# power_supply-TPS54531.net
KiCad netlist of a schematic drawn in EAGLE
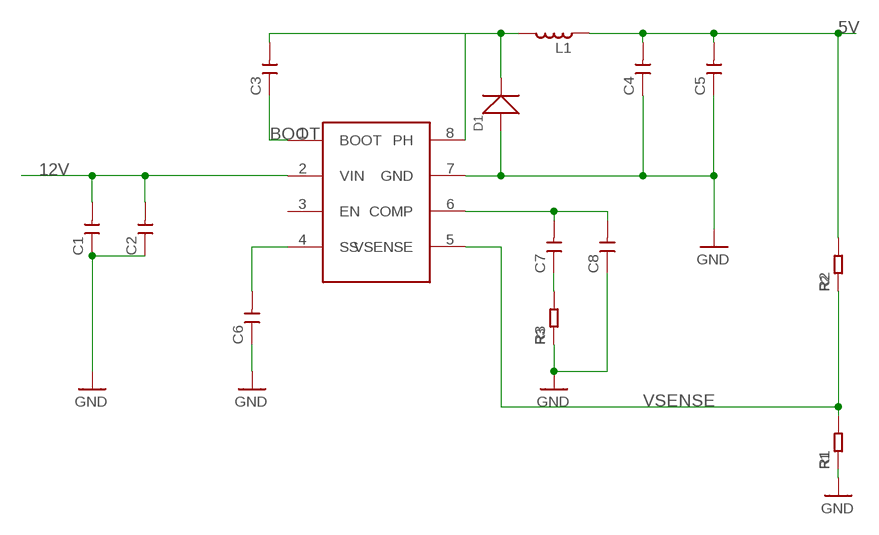
[diagram p0: schematic, sheet 1]

(export (version "E")
  (design (tool "Eeschema 10.0.6"))
  (components
    (comp (ref "C1")
      (value "CAP-CERAMIC-SMD0805")
      (footprint "eagle-import:0805")
      (libsource (lib "eagle-import") (part "CAP-CERAMIC-SMD0805"))
    )
    (comp (ref "C2")
      (value "CAP-CERAMIC-SMD0805")
      (footprint "eagle-import:0805")
      (libsource (lib "eagle-import") (part "CAP-CERAMIC-SMD0805"))
    )
    (comp (ref "C3")
      (value "CAP-CERAMIC-SMD0805")
      (footprint "eagle-import:0805")
      (libsource (lib "eagle-import") (part "CAP-CERAMIC-SMD0805"))
    )
    (comp (ref "C4")
      (value "CAP-CERAMIC-SMD0805")
      (footprint "eagle-import:0805")
      (libsource (lib "eagle-import") (part "CAP-CERAMIC-SMD0805"))
    )
    (comp (ref "C5")
      (value "CAP-CERAMIC-SMD0805")
      (footprint "eagle-import:0805")
      (libsource (lib "eagle-import") (part "CAP-CERAMIC-SMD0805"))
    )
    (comp (ref "C6")
      (value "CAP-CERAMIC-SMD0805")
      (footprint "eagle-import:0805")
      (libsource (lib "eagle-import") (part "CAP-CERAMIC-SMD0805"))
    )
    (comp (ref "C7")
      (value "CAP-CERAMIC-SMD0805")
      (footprint "eagle-import:0805")
      (libsource (lib "eagle-import") (part "CAP-CERAMIC-SMD0805"))
    )
    (comp (ref "C8")
      (value "CAP-CERAMIC-SMD0805")
      (footprint "eagle-import:0805")
      (libsource (lib "eagle-import") (part "CAP-CERAMIC-SMD0805"))
    )
    (comp (ref "D1")
      (value "SMD-DIODE-SCHOTTKY-28V-5A(DO-214AA)DO-214AC")
      (footprint "eagle-import:SMA-DO214AC")
      (fields (field (name "MANUFACTURER") "Comchip Technologies") (field (name "PARTNO") "CDBA540-HF"))
      (libsource (lib "eagle-import") (part "SMD-DIODE-SCHOTTKY-28V-5A(DO-214AA)DO-214AC"))
    )
    (comp (ref "L1")
      (value "IND-TDK-SPM6530T")
      (footprint "eagle-import:IND_TDK_7.1X6.5")
      (fields (field (name "MANUFACTURER") "TDK") (field (name "PARTNO") "SPM6530T-4R7M "))
      (libsource (lib "eagle-import") (part "IND-TDK-SPM6530T"))
    )
    (comp (ref "R1")
      (value "RES-SMD-0805")
      (footprint "eagle-import:0805")
      (libsource (lib "eagle-import") (part "RES-SMD-0805"))
    )
    (comp (ref "R2")
      (value "RES-SMD-0805")
      (footprint "eagle-import:0805")
      (libsource (lib "eagle-import") (part "RES-SMD-0805"))
    )
    (comp (ref "R3")
      (value "RES-SMD-0805")
      (footprint "eagle-import:0805")
      (libsource (lib "eagle-import") (part "RES-SMD-0805"))
    )
    (comp (ref "U$1")
      (value "TPS54531SOIC8")
      (footprint "eagle-import:SOIC8")
      (fields (field (name "MANUFACTURER") "TEXAS INSTRUMENTS") (field (name "PARTNO") "TPS54531DDAR"))
      (libsource (lib "eagle-import") (part "TPS54531SOIC8"))
    )
  )
  (nets
    (net (code "1") (name "/5V") (class "Default")
      (node (ref "C4") (pin "2") (pinfunction "2_2") (pintype "passive"))
      (node (ref "C5") (pin "2") (pinfunction "2_2") (pintype "passive"))
      (node (ref "L1") (pin "1") (pinfunction "1_1") (pintype "passive"))
      (node (ref "R2") (pin "2") (pinfunction "2_2") (pintype "passive"))
    )
    (net (code "2") (name "/12V") (class "Default")
      (node (ref "C1") (pin "2") (pinfunction "2_2") (pintype "passive"))
      (node (ref "C2") (pin "2") (pinfunction "2_2") (pintype "passive"))
      (node (ref "U$1") (pin "2") (pinfunction "VIN_2") (pintype "power_in"))
    )
    (net (code "3") (name "/BOOT") (class "Default")
      (node (ref "C3") (pin "1") (pinfunction "1_1") (pintype "passive"))
      (node (ref "U$1") (pin "1") (pinfunction "BOOT_1") (pintype "bidirectional"))
    )
    (net (code "4") (name "/VSENSE") (class "Default")
      (node (ref "R1") (pin "2") (pinfunction "2_2") (pintype "passive"))
      (node (ref "R2") (pin "1") (pinfunction "1_1") (pintype "passive"))
      (node (ref "U$1") (pin "5") (pinfunction "VSENSE_5") (pintype "bidirectional"))
    )
    (net (code "5") (name "GND") (class "Default")
      (node (ref "C1") (pin "1") (pinfunction "1_1") (pintype "passive"))
      (node (ref "C2") (pin "1") (pinfunction "1_1") (pintype "passive"))
      (node (ref "C4") (pin "1") (pinfunction "1_1") (pintype "passive"))
      (node (ref "C5") (pin "1") (pinfunction "1_1") (pintype "passive"))
      (node (ref "C6") (pin "1") (pinfunction "1_1") (pintype "passive"))
      (node (ref "C8") (pin "1") (pinfunction "1_1") (pintype "passive"))
      (node (ref "D1") (pin "A") (pinfunction "+_A") (pintype "passive"))
      (node (ref "R1") (pin "1") (pinfunction "1_1") (pintype "passive"))
      (node (ref "R3") (pin "1") (pinfunction "1_1") (pintype "passive"))
      (node (ref "U$1") (pin "7") (pinfunction "GND_7") (pintype "bidirectional"))
    )
    (net (code "6") (name "Net-(C7-Pad1)") (class "Default")
      (node (ref "C7") (pin "1") (pinfunction "1_1") (pintype "passive"))
      (node (ref "R3") (pin "2") (pinfunction "2_2") (pintype "passive"))
    )
    (net (code "7") (name "Net-(D1--)") (class "Default")
      (node (ref "C3") (pin "2") (pinfunction "2_2") (pintype "passive"))
      (node (ref "D1") (pin "K") (pinfunction "-_K") (pintype "passive"))
      (node (ref "L1") (pin "2") (pinfunction "2_2") (pintype "passive"))
      (node (ref "U$1") (pin "8") (pinfunction "PH_8") (pintype "bidirectional"))
    )
    (net (code "8") (name "Net-(U$1-COMP)") (class "Default")
      (node (ref "C7") (pin "2") (pinfunction "2_2") (pintype "passive"))
      (node (ref "C8") (pin "2") (pinfunction "2_2") (pintype "passive"))
      (node (ref "U$1") (pin "6") (pinfunction "COMP_6") (pintype "bidirectional"))
    )
    (net (code "9") (name "Net-(U$1-SS)") (class "Default")
      (node (ref "C6") (pin "2") (pinfunction "2_2") (pintype "passive"))
      (node (ref "U$1") (pin "4") (pinfunction "SS_4") (pintype "bidirectional"))
    )
    (net (code "10") (name "unconnected-(U$1-EN-Pad3)") (class "Default")
      (node (ref "U$1") (pin "3") (pinfunction "EN_3") (pintype "bidirectional"))
    )
  )
)
